# equaliser_TDA7418.net
KiCad netlist of a schematic drawn in EAGLE
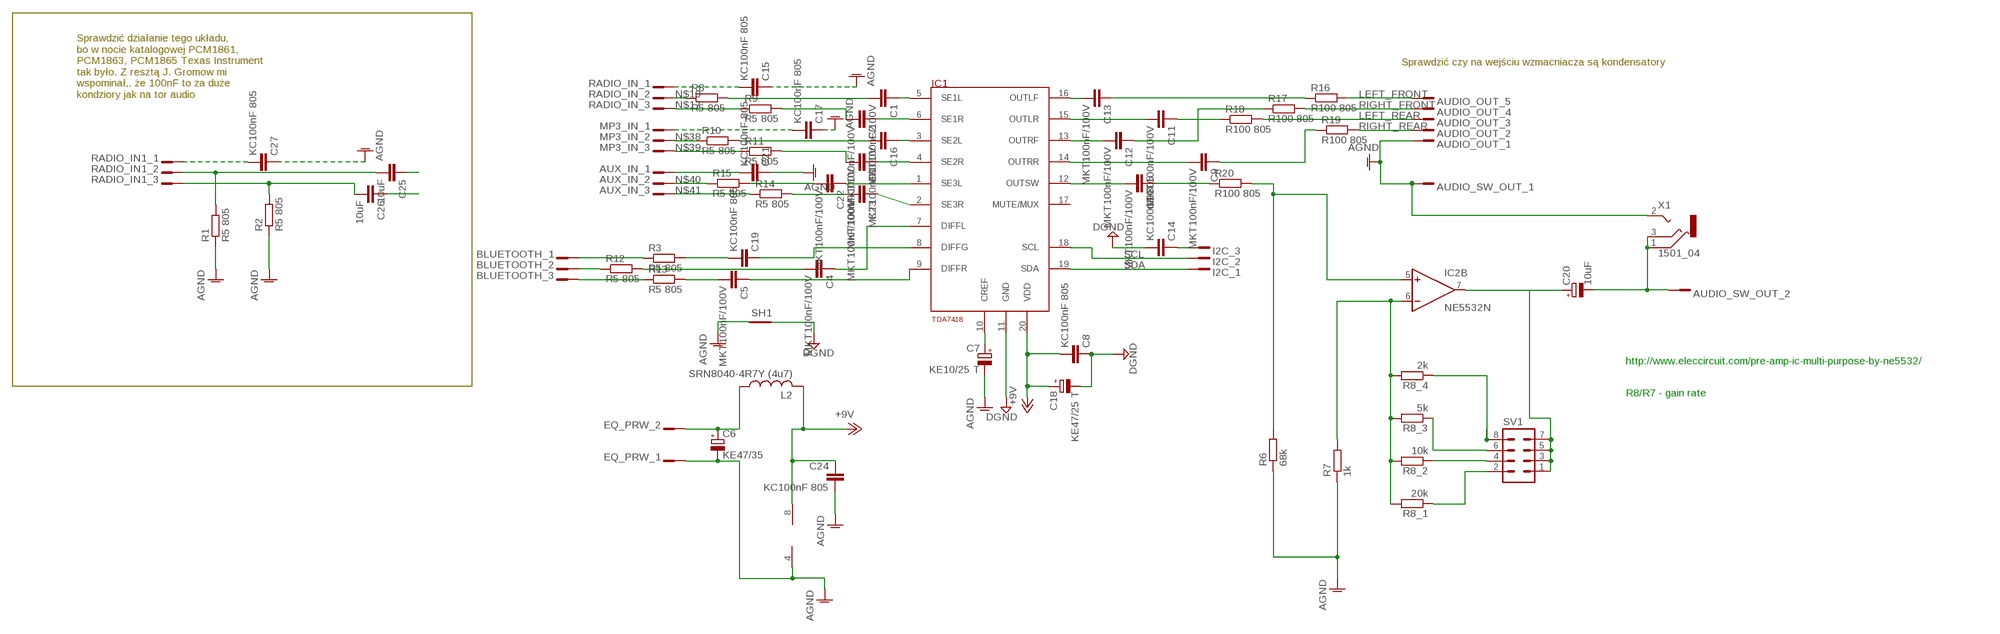
[diagram p0: schematic, sheet 1]

(export (version "E")
  (design (tool "Eeschema 10.0.6"))
  (components
    (comp (ref "AUDIO_OUT")
      (value "JST_5_PIN_B5B-PH-KS")
      (footprint "eagle-import:B5B-PH-KS")
      (libsource (lib "eagle-import") (part "JST_5_PIN_B5B-PH-KS"))
    )
    (comp (ref "AUDIO_SW_OUT")
      (value "JST_2_PIN_B2B-PH-KS")
      (footprint "eagle-import:B2B-PH-KS")
      (libsource (lib "eagle-import") (part "JST_2_PIN_B2B-PH-KS"))
    )
    (comp (ref "AUX_IN")
      (value "JST_3_PIN_B3B-PH-KS")
      (footprint "eagle-import:B3B-PH-KS")
      (libsource (lib "eagle-import") (part "JST_3_PIN_B3B-PH-KS"))
    )
    (comp (ref "BLUETOOTH")
      (value "JST_3_PIN_B3B-PH-KS")
      (footprint "eagle-import:B3B-PH-KS")
      (libsource (lib "eagle-import") (part "JST_3_PIN_B3B-PH-KS"))
    )
    (comp (ref "C1")
      (value "MKT100nF/100V")
      (footprint "eagle-import:C050-035X075")
      (libsource (lib "eagle-import") (part "C-EU050-035X075"))
    )
    (comp (ref "C2")
      (value "MKT100nF/100V")
      (footprint "eagle-import:C050-035X075")
      (libsource (lib "eagle-import") (part "C-EU050-035X075"))
    )
    (comp (ref "C3")
      (value "MKT100nF/100V")
      (footprint "eagle-import:C050-035X075")
      (libsource (lib "eagle-import") (part "C-EU050-035X075"))
    )
    (comp (ref "C4")
      (value "MKT100nF/100V")
      (footprint "eagle-import:C050-035X075")
      (libsource (lib "eagle-import") (part "C-EU050-035X075"))
    )
    (comp (ref "C5")
      (value "MKT100nF/100V")
      (footprint "eagle-import:C050-035X075")
      (libsource (lib "eagle-import") (part "C-EU050-035X075"))
    )
    (comp (ref "C6")
      (value "KE47/35")
      (footprint "eagle-import:TT2D6")
      (libsource (lib "eagle-import") (part "CPOL-EUTT2D6"))
    )
    (comp (ref "C7")
      (value "KE10/25 T")
      (footprint "eagle-import:E1,8-4")
      (libsource (lib "eagle-import") (part "resistor_CPOL-EUE1.8-4"))
    )
    (comp (ref "C8")
      (value "KC100nF 805")
      (footprint "eagle-import:C0805")
      (libsource (lib "eagle-import") (part "C-EUC0805"))
    )
    (comp (ref "C9")
      (value "MKT100nF/100V")
      (footprint "eagle-import:C050-035X075")
      (libsource (lib "eagle-import") (part "C-EU050-035X075"))
    )
    (comp (ref "C10")
      (value "MKT100nF/100V")
      (footprint "eagle-import:C050-035X075")
      (libsource (lib "eagle-import") (part "C-EU050-035X075"))
    )
    (comp (ref "C11")
      (value "MKT100nF/100V")
      (footprint "eagle-import:C050-035X075")
      (libsource (lib "eagle-import") (part "C-EU050-035X075"))
    )
    (comp (ref "C12")
      (value "MKT100nF/100V")
      (footprint "eagle-import:C050-035X075")
      (libsource (lib "eagle-import") (part "C-EU050-035X075"))
    )
    (comp (ref "C13")
      (value "MKT100nF/100V")
      (footprint "eagle-import:C050-035X075")
      (libsource (lib "eagle-import") (part "C-EU050-035X075"))
    )
    (comp (ref "C14")
      (value "KC100nF 805")
      (footprint "eagle-import:C0805")
      (libsource (lib "eagle-import") (part "C-EUC0805"))
    )
    (comp (ref "C15")
      (value "KC100nF 805")
      (footprint "eagle-import:C0805")
      (libsource (lib "eagle-import") (part "C-EUC0805"))
    )
    (comp (ref "C16")
      (value "MKT100nF/100V")
      (footprint "eagle-import:C050-035X075")
      (libsource (lib "eagle-import") (part "C-EU050-035X075"))
    )
    (comp (ref "C17")
      (value "KC100nF 805")
      (footprint "eagle-import:C0805")
      (libsource (lib "eagle-import") (part "C-EUC0805"))
    )
    (comp (ref "C18")
      (value "KE47/25 T")
      (footprint "eagle-import:B45181B")
      (libsource (lib "eagle-import") (part "CPOL-EUB45181B"))
    )
    (comp (ref "C19")
      (value "KC100nF 805")
      (footprint "eagle-import:C0805")
      (libsource (lib "eagle-import") (part "C-EUC0805"))
    )
    (comp (ref "C20")
      (value "10uF")
      (footprint "eagle-import:TT2D6")
      (libsource (lib "eagle-import") (part "CPOL-EUTT2D6"))
    )
    (comp (ref "C21")
      (value "KC100nF 805")
      (footprint "eagle-import:C0805")
      (libsource (lib "eagle-import") (part "C-EUC0805"))
    )
    (comp (ref "C22")
      (value "MKT100nF/100V")
      (footprint "eagle-import:C050-035X075")
      (libsource (lib "eagle-import") (part "C-EU050-035X075"))
    )
    (comp (ref "C23")
      (value "MKT100nF/100V")
      (footprint "eagle-import:C050-035X075")
      (libsource (lib "eagle-import") (part "C-EU050-035X075"))
    )
    (comp (ref "C24")
      (value "KC100nF 805")
      (footprint "eagle-import:C0805")
      (libsource (lib "eagle-import") (part "C-EUC0805"))
    )
    (comp (ref "C25")
      (value "10uF")
      (footprint "eagle-import:C050-035X075")
      (libsource (lib "eagle-import") (part "C-EU050-035X075"))
    )
    (comp (ref "C26")
      (value "10uF")
      (footprint "eagle-import:C050-035X075")
      (libsource (lib "eagle-import") (part "C-EU050-035X075"))
    )
    (comp (ref "C27")
      (value "KC100nF 805")
      (footprint "eagle-import:C0805")
      (libsource (lib "eagle-import") (part "C-EUC0805"))
    )
    (comp (ref "EQ_PRW")
      (value "JST_2_PIN_B2B-XH-A")
      (footprint "eagle-import:B2B-XH-A")
      (libsource (lib "eagle-import") (part "JST_2_PIN_B2B-XH-A"))
    )
    (comp (ref "I2C")
      (value "JST_3_PIN_B3B-PH-KS")
      (footprint "eagle-import:B3B-PH-KS")
      (libsource (lib "eagle-import") (part "JST_3_PIN_B3B-PH-KS"))
    )
    (comp (ref "IC1")
      (value "TDA7418")
      (footprint "eagle-import:SO20")
      (libsource (lib "eagle-import") (part "TDA7418"))
    )
    (comp (ref "IC2")
      (value "NE5532N")
      (footprint "eagle-import:DIL08")
      (libsource (lib "eagle-import") (part "NE5532N"))
    )
    (comp (ref "L2")
      (value "SRN8040-4R7Y (4u7)")
      (footprint "eagle-import:0204_5")
      (libsource (lib "eagle-import") (part "L-US0204/5"))
    )
    (comp (ref "MP3_IN")
      (value "JST_3_PIN_B3B-PH-KS")
      (footprint "eagle-import:B3B-PH-KS")
      (libsource (lib "eagle-import") (part "JST_3_PIN_B3B-PH-KS"))
    )
    (comp (ref "R1")
      (value "R5 805")
      (footprint "eagle-import:R0805")
      (libsource (lib "eagle-import") (part "R-EU_R0805"))
    )
    (comp (ref "R2")
      (value "R5 805")
      (footprint "eagle-import:R0805")
      (libsource (lib "eagle-import") (part "R-EU_R0805"))
    )
    (comp (ref "R3")
      (value "R5 805")
      (footprint "eagle-import:R0805")
      (libsource (lib "eagle-import") (part "R-EU_R0805"))
    )
    (comp (ref "R6")
      (value "68k")
      (footprint "eagle-import:R0805")
      (libsource (lib "eagle-import") (part "R-EU_R0805"))
    )
    (comp (ref "R7")
      (value "1k")
      (footprint "eagle-import:R0805")
      (libsource (lib "eagle-import") (part "R-EU_R0805"))
    )
    (comp (ref "R8")
      (value "R5 805")
      (footprint "eagle-import:R0805")
      (libsource (lib "eagle-import") (part "R-EU_R0805"))
    )
    (comp (ref "R8_1")
      (value "20k")
      (footprint "eagle-import:R0805")
      (libsource (lib "eagle-import") (part "R-EU_R0805"))
    )
    (comp (ref "R8_2")
      (value "10k")
      (footprint "eagle-import:R0805")
      (libsource (lib "eagle-import") (part "R-EU_R0805"))
    )
    (comp (ref "R8_3")
      (value "5k")
      (footprint "eagle-import:R0805")
      (libsource (lib "eagle-import") (part "R-EU_R0805"))
    )
    (comp (ref "R8_4")
      (value "2k")
      (footprint "eagle-import:R0805")
      (libsource (lib "eagle-import") (part "R-EU_R0805"))
    )
    (comp (ref "R9")
      (value "R5 805")
      (footprint "eagle-import:R0805")
      (libsource (lib "eagle-import") (part "R-EU_R0805"))
    )
    (comp (ref "R10")
      (value "R5 805")
      (footprint "eagle-import:R0805")
      (libsource (lib "eagle-import") (part "R-EU_R0805"))
    )
    (comp (ref "R11")
      (value "R5 805")
      (footprint "eagle-import:R0805")
      (libsource (lib "eagle-import") (part "R-EU_R0805"))
    )
    (comp (ref "R12")
      (value "R5 805")
      (footprint "eagle-import:R0805")
      (libsource (lib "eagle-import") (part "R-EU_R0805"))
    )
    (comp (ref "R13")
      (value "R5 805")
      (footprint "eagle-import:R0805")
      (libsource (lib "eagle-import") (part "R-EU_R0805"))
    )
    (comp (ref "R14")
      (value "R5 805")
      (footprint "eagle-import:R0805")
      (libsource (lib "eagle-import") (part "R-EU_R0805"))
    )
    (comp (ref "R15")
      (value "R5 805")
      (footprint "eagle-import:R0805")
      (libsource (lib "eagle-import") (part "R-EU_R0805"))
    )
    (comp (ref "R16")
      (value "R100 805")
      (footprint "eagle-import:R0805")
      (libsource (lib "eagle-import") (part "R-EU_R0805"))
    )
    (comp (ref "R17")
      (value "R100 805")
      (footprint "eagle-import:R0805")
      (libsource (lib "eagle-import") (part "R-EU_R0805"))
    )
    (comp (ref "R18")
      (value "R100 805")
      (footprint "eagle-import:R0805")
      (libsource (lib "eagle-import") (part "R-EU_R0805"))
    )
    (comp (ref "R19")
      (value "R100 805")
      (footprint "eagle-import:R0805")
      (libsource (lib "eagle-import") (part "R-EU_R0805"))
    )
    (comp (ref "R20")
      (value "R100 805")
      (footprint "eagle-import:R0805")
      (libsource (lib "eagle-import") (part "R-EU_R0805"))
    )
    (comp (ref "RADIO_IN")
      (value "JST_3_PIN_B3B-PH-KS")
      (footprint "eagle-import:B3B-PH-KS")
      (libsource (lib "eagle-import") (part "JST_3_PIN_B3B-PH-KS"))
    )
    (comp (ref "RADIO_IN1")
      (value "JST_3_PIN_B3B-PH-KS")
      (footprint "eagle-import:B3B-PH-KS")
      (libsource (lib "eagle-import") (part "JST_3_PIN_B3B-PH-KS"))
    )
    (comp (ref "SH1")
      (value "SHORT-HT5")
      (footprint "eagle-import:SHORT_TOP-50")
      (libsource (lib "eagle-import") (part "SHORT-HT5"))
    )
    (comp (ref "SV1")
      (value "MA04-2")
      (footprint "eagle-import:MA04-2")
      (libsource (lib "eagle-import") (part "MA04-2"))
    )
    (comp (ref "X1")
      (value "1501_04")
      (footprint "eagle-import:1501_05")
      (libsource (lib "eagle-import") (part "1501_04"))
    )
  )
  (nets
    (net (code "1") (name "+9V") (class "Default")
      (node (ref "C18") (pin "+") (pinfunction "+_+") (pintype "passive"))
      (node (ref "C24") (pin "1") (pinfunction "1_1") (pintype "passive"))
      (node (ref "C8") (pin "2") (pinfunction "2_2") (pintype "passive"))
      (node (ref "IC1") (pin "20") (pinfunction "VDD_20") (pintype "bidirectional"))
      (node (ref "IC2") (pin "8") (pinfunction "V+_8") (pintype "power_in"))
      (node (ref "L2") (pin "2") (pinfunction "2_2") (pintype "passive"))
    )
    (net (code "2") (name "/LEFT_FRONT") (class "Default")
      (node (ref "AUDIO_OUT") (pin "P$5") (pinfunction "P$1_P$5") (pintype "bidirectional"))
      (node (ref "R16") (pin "2") (pinfunction "2_2") (pintype "passive"))
    )
    (net (code "3") (name "/LEFT_REAR") (class "Default")
      (node (ref "AUDIO_OUT") (pin "P$3") (pinfunction "P$1_P$3") (pintype "bidirectional"))
      (node (ref "R18") (pin "2") (pinfunction "2_2") (pintype "passive"))
    )
    (net (code "4") (name "/N$10") (class "Default")
      (node (ref "R8") (pin "1") (pinfunction "1_1") (pintype "passive"))
      (node (ref "RADIO_IN") (pin "P$2") (pinfunction "P$1_P$2") (pintype "bidirectional"))
    )
    (net (code "5") (name "/N$17") (class "Default")
      (node (ref "R9") (pin "1") (pinfunction "1_1") (pintype "passive"))
      (node (ref "RADIO_IN") (pin "P$3") (pinfunction "P$1_P$3") (pintype "bidirectional"))
    )
    (net (code "6") (name "/N$38") (class "Default")
      (node (ref "MP3_IN") (pin "P$2") (pinfunction "P$1_P$2") (pintype "bidirectional"))
      (node (ref "R10") (pin "1") (pinfunction "1_1") (pintype "passive"))
    )
    (net (code "7") (name "/N$39") (class "Default")
      (node (ref "MP3_IN") (pin "P$3") (pinfunction "P$1_P$3") (pintype "bidirectional"))
      (node (ref "R11") (pin "1") (pinfunction "1_1") (pintype "passive"))
    )
    (net (code "8") (name "/N$40") (class "Default")
      (node (ref "BLUETOOTH") (pin "P$2") (pinfunction "P$1_P$2") (pintype "bidirectional"))
      (node (ref "R12") (pin "1") (pinfunction "1_1") (pintype "passive"))
    )
    (net (code "9") (name "/N$41") (class "Default")
      (node (ref "BLUETOOTH") (pin "P$3") (pinfunction "P$1_P$3") (pintype "bidirectional"))
      (node (ref "R13") (pin "1") (pinfunction "1_1") (pintype "passive"))
    )
    (net (code "10") (name "/RIGHT_FRONT") (class "Default")
      (node (ref "AUDIO_OUT") (pin "P$4") (pinfunction "P$1_P$4") (pintype "bidirectional"))
      (node (ref "R17") (pin "2") (pinfunction "2_2") (pintype "passive"))
    )
    (net (code "11") (name "/RIGHT_REAR") (class "Default")
      (node (ref "AUDIO_OUT") (pin "P$2") (pinfunction "P$1_P$2") (pintype "bidirectional"))
      (node (ref "R19") (pin "2") (pinfunction "2_2") (pintype "passive"))
    )
    (net (code "12") (name "/SCL") (class "Default")
      (node (ref "I2C") (pin "P$2") (pinfunction "P$1_P$2") (pintype "bidirectional"))
      (node (ref "IC1") (pin "18") (pinfunction "SCL_18") (pintype "bidirectional"))
    )
    (net (code "13") (name "/SDA") (class "Default")
      (node (ref "I2C") (pin "P$1") (pinfunction "P$1_P$1") (pintype "bidirectional"))
      (node (ref "IC1") (pin "19") (pinfunction "SDA_19") (pintype "bidirectional"))
    )
    (net (code "14") (name "AGND") (class "Default")
      (node (ref "AUDIO_OUT") (pin "P$1") (pinfunction "P$1_P$1") (pintype "bidirectional"))
      (node (ref "AUDIO_SW_OUT") (pin "P$1") (pinfunction "P$1_P$1") (pintype "bidirectional"))
      (node (ref "C15") (pin "1") (pinfunction "1_1") (pintype "passive"))
      (node (ref "C17") (pin "1") (pinfunction "1_1") (pintype "passive"))
      (node (ref "C21") (pin "1") (pinfunction "1_1") (pintype "passive"))
      (node (ref "C24") (pin "2") (pinfunction "2_2") (pintype "passive"))
      (node (ref "C27") (pin "1") (pinfunction "1_1") (pintype "passive"))
      (node (ref "C6") (pin "-") (pinfunction "-_-") (pintype "passive"))
      (node (ref "C7") (pin "-") (pinfunction "-_-") (pintype "passive"))
      (node (ref "EQ_PRW") (pin "P$1") (pinfunction "P$1_P$1") (pintype "bidirectional"))
      (node (ref "IC2") (pin "4") (pinfunction "V-_4") (pintype "power_in"))
      (node (ref "R1") (pin "1") (pinfunction "1_1") (pintype "passive"))
      (node (ref "R2") (pin "1") (pinfunction "1_1") (pintype "passive"))
      (node (ref "R6") (pin "1") (pinfunction "1_1") (pintype "passive"))
      (node (ref "R7") (pin "1") (pinfunction "1_1") (pintype "passive"))
      (node (ref "SH1") (pin "1") (pinfunction "P$1_1") (pintype "bidirectional"))
      (node (ref "X1") (pin "2") (pinfunction "2_2") (pintype "passive"))
    )
    (net (code "15") (name "DGND") (class "Default")
      (node (ref "C14") (pin "2") (pinfunction "2_2") (pintype "passive"))
      (node (ref "C18") (pin "-") (pinfunction "-_-") (pintype "passive"))
      (node (ref "C8") (pin "1") (pinfunction "1_1") (pintype "passive"))
      (node (ref "IC1") (pin "11") (pinfunction "GND_11") (pintype "bidirectional"))
      (node (ref "SH1") (pin "2") (pinfunction "P$2_2") (pintype "bidirectional"))
    )
    (net (code "16") (name "Net-(AUDIO_SW_OUTB-P$1)") (class "Default")
      (node (ref "AUDIO_SW_OUT") (pin "P$2") (pinfunction "P$1_P$2") (pintype "bidirectional"))
      (node (ref "C20") (pin "-") (pinfunction "-_-") (pintype "passive"))
      (node (ref "X1") (pin "1") (pinfunction "1_1") (pintype "passive"))
      (node (ref "X1") (pin "3") (pinfunction "3_3") (pintype "passive"))
    )
    (net (code "17") (name "Net-(AUX_IN-PadP$1)") (class "Default")
      (node (ref "AUX_IN") (pin "P$1") (pinfunction "P$1_P$1") (pintype "bidirectional"))
      (node (ref "C21") (pin "2") (pinfunction "2_2") (pintype "passive"))
    )
    (net (code "18") (name "Net-(AUX_INB-P$1)") (class "Default")
      (node (ref "AUX_IN") (pin "P$2") (pinfunction "P$1_P$2") (pintype "bidirectional"))
      (node (ref "R15") (pin "1") (pinfunction "1_1") (pintype "passive"))
    )
    (net (code "19") (name "Net-(AUX_INC-P$1)") (class "Default")
      (node (ref "AUX_IN") (pin "P$3") (pinfunction "P$1_P$3") (pintype "bidirectional"))
      (node (ref "R14") (pin "1") (pinfunction "1_1") (pintype "passive"))
    )
    (net (code "20") (name "Net-(BLUETOOTH-PadP$1)") (class "Default")
      (node (ref "BLUETOOTH") (pin "P$1") (pinfunction "P$1_P$1") (pintype "bidirectional"))
      (node (ref "R3") (pin "1") (pinfunction "1_1") (pintype "passive"))
    )
    (net (code "21") (name "Net-(C1-Pad2)") (class "Default")
      (node (ref "C1") (pin "2") (pinfunction "2_2") (pintype "passive"))
      (node (ref "R8") (pin "2") (pinfunction "2_2") (pintype "passive"))
    )
    (net (code "22") (name "Net-(C2-Pad2)") (class "Default")
      (node (ref "C2") (pin "2") (pinfunction "2_2") (pintype "passive"))
      (node (ref "R9") (pin "2") (pinfunction "2_2") (pintype "passive"))
    )
    (net (code "23") (name "Net-(C3-Pad2)") (class "Default")
      (node (ref "C3") (pin "2") (pinfunction "2_2") (pintype "passive"))
      (node (ref "R11") (pin "2") (pinfunction "2_2") (pintype "passive"))
    )
    (net (code "24") (name "Net-(C4-Pad2)") (class "Default")
      (node (ref "C4") (pin "2") (pinfunction "2_2") (pintype "passive"))
      (node (ref "R12") (pin "2") (pinfunction "2_2") (pintype "passive"))
    )
    (net (code "25") (name "Net-(C5-Pad2)") (class "Default")
      (node (ref "C5") (pin "2") (pinfunction "2_2") (pintype "passive"))
      (node (ref "R13") (pin "2") (pinfunction "2_2") (pintype "passive"))
    )
    (net (code "26") (name "Net-(C9-Pad1)") (class "Default")
      (node (ref "C9") (pin "1") (pinfunction "1_1") (pintype "passive"))
      (node (ref "R19") (pin "1") (pinfunction "1_1") (pintype "passive"))
    )
    (net (code "27") (name "Net-(C10-Pad1)") (class "Default")
      (node (ref "C10") (pin "1") (pinfunction "1_1") (pintype "passive"))
      (node (ref "R20") (pin "1") (pinfunction "1_1") (pintype "passive"))
    )
    (net (code "28") (name "Net-(C11-Pad1)") (class "Default")
      (node (ref "C11") (pin "1") (pinfunction "1_1") (pintype "passive"))
      (node (ref "R18") (pin "1") (pinfunction "1_1") (pintype "passive"))
    )
    (net (code "29") (name "Net-(C12-Pad1)") (class "Default")
      (node (ref "C12") (pin "1") (pinfunction "1_1") (pintype "passive"))
      (node (ref "R17") (pin "1") (pinfunction "1_1") (pintype "passive"))
    )
    (net (code "30") (name "Net-(C13-Pad1)") (class "Default")
      (node (ref "C13") (pin "1") (pinfunction "1_1") (pintype "passive"))
      (node (ref "R16") (pin "1") (pinfunction "1_1") (pintype "passive"))
    )
    (net (code "31") (name "Net-(C15-Pad2)") (class "Default")
      (node (ref "C15") (pin "2") (pinfunction "2_2") (pintype "passive"))
      (node (ref "RADIO_IN") (pin "P$1") (pinfunction "P$1_P$1") (pintype "bidirectional"))
    )
    (net (code "32") (name "Net-(C16-Pad2)") (class "Default")
      (node (ref "C16") (pin "2") (pinfunction "2_2") (pintype "passive"))
      (node (ref "R10") (pin "2") (pinfunction "2_2") (pintype "passive"))
    )
    (net (code "33") (name "Net-(C17-Pad2)") (class "Default")
      (node (ref "C17") (pin "2") (pinfunction "2_2") (pintype "passive"))
      (node (ref "MP3_IN") (pin "P$1") (pinfunction "P$1_P$1") (pintype "bidirectional"))
    )
    (net (code "34") (name "Net-(C19-Pad2)") (class "Default")
      (node (ref "C19") (pin "2") (pinfunction "2_2") (pintype "passive"))
      (node (ref "R3") (pin "2") (pinfunction "2_2") (pintype "passive"))
    )
    (net (code "35") (name "Net-(C22-Pad2)") (class "Default")
      (node (ref "C22") (pin "2") (pinfunction "2_2") (pintype "passive"))
      (node (ref "R15") (pin "2") (pinfunction "2_2") (pintype "passive"))
    )
    (net (code "36") (name "Net-(C23-Pad2)") (class "Default")
      (node (ref "C23") (pin "2") (pinfunction "2_2") (pintype "passive"))
      (node (ref "R14") (pin "2") (pinfunction "2_2") (pintype "passive"))
    )
    (net (code "37") (name "Net-(C27-Pad2)") (class "Default")
      (node (ref "C27") (pin "2") (pinfunction "2_2") (pintype "passive"))
      (node (ref "RADIO_IN1") (pin "P$1") (pinfunction "P$1_P$1") (pintype "bidirectional"))
    )
    (net (code "38") (name "Net-(EQ_PRWB-P$1)") (class "Default")
      (node (ref "C6") (pin "+") (pinfunction "+_+") (pintype "passive"))
      (node (ref "EQ_PRW") (pin "P$2") (pinfunction "P$1_P$2") (pintype "bidirectional"))
      (node (ref "L2") (pin "1") (pinfunction "1_1") (pintype "passive"))
    )
    (net (code "39") (name "Net-(I2CC-P$1)") (class "Default")
      (node (ref "C14") (pin "1") (pinfunction "1_1") (pintype "passive"))
      (node (ref "I2C") (pin "P$3") (pinfunction "P$1_P$3") (pintype "bidirectional"))
    )
    (net (code "40") (name "Net-(IC1-CREF)") (class "Default")
      (node (ref "C7") (pin "+") (pinfunction "+_+") (pintype "passive"))
      (node (ref "IC1") (pin "10") (pinfunction "CREF_10") (pintype "bidirectional"))
    )
    (net (code "41") (name "Net-(IC1-DIFFG)") (class "Default")
      (node (ref "C19") (pin "1") (pinfunction "1_1") (pintype "passive"))
      (node (ref "IC1") (pin "8") (pinfunction "DIFFG_8") (pintype "bidirectional"))
    )
    (net (code "42") (name "Net-(IC1-DIFFL)") (class "Default")
      (node (ref "C4") (pin "1") (pinfunction "1_1") (pintype "passive"))
      (node (ref "IC1") (pin "7") (pinfunction "DIFFL_7") (pintype "bidirectional"))
    )
    (net (code "43") (name "Net-(IC1-DIFFR)") (class "Default")
      (node (ref "C5") (pin "1") (pinfunction "1_1") (pintype "passive"))
      (node (ref "IC1") (pin "9") (pinfunction "DIFFR_9") (pintype "bidirectional"))
    )
    (net (code "44") (name "Net-(IC1-OUTLF)") (class "Default")
      (node (ref "C13") (pin "2") (pinfunction "2_2") (pintype "passive"))
      (node (ref "IC1") (pin "16") (pinfunction "OUTLF_16") (pintype "bidirectional"))
    )
    (net (code "45") (name "Net-(IC1-OUTLR)") (class "Default")
      (node (ref "C11") (pin "2") (pinfunction "2_2") (pintype "passive"))
      (node (ref "IC1") (pin "15") (pinfunction "OUTLR_15") (pintype "bidirectional"))
    )
    (net (code "46") (name "Net-(IC1-OUTRF)") (class "Default")
      (node (ref "C12") (pin "2") (pinfunction "2_2") (pintype "passive"))
      (node (ref "IC1") (pin "13") (pinfunction "OUTRF_13") (pintype "bidirectional"))
    )
    (net (code "47") (name "Net-(IC1-OUTRR)") (class "Default")
      (node (ref "C9") (pin "2") (pinfunction "2_2") (pintype "passive"))
      (node (ref "IC1") (pin "14") (pinfunction "OUTRR_14") (pintype "bidirectional"))
    )
    (net (code "48") (name "Net-(IC1-OUTSW)") (class "Default")
      (node (ref "C10") (pin "2") (pinfunction "2_2") (pintype "passive"))
      (node (ref "IC1") (pin "12") (pinfunction "OUTSW_12") (pintype "bidirectional"))
    )
    (net (code "49") (name "Net-(IC1-SE1L)") (class "Default")
      (node (ref "C1") (pin "1") (pinfunction "1_1") (pintype "passive"))
      (node (ref "IC1") (pin "5") (pinfunction "SE1L_5") (pintype "bidirectional"))
    )
    (net (code "50") (name "Net-(IC1-SE1R)") (class "Default")
      (node (ref "C2") (pin "1") (pinfunction "1_1") (pintype "passive"))
      (node (ref "IC1") (pin "6") (pinfunction "SE1R_6") (pintype "bidirectional"))
    )
    (net (code "51") (name "Net-(IC1-SE2L)") (class "Default")
      (node (ref "C16") (pin "1") (pinfunction "1_1") (pintype "passive"))
      (node (ref "IC1") (pin "3") (pinfunction "SE2L_3") (pintype "bidirectional"))
    )
    (net (code "52") (name "Net-(IC1-SE2R)") (class "Default")
      (node (ref "C3") (pin "1") (pinfunction "1_1") (pintype "passive"))
      (node (ref "IC1") (pin "4") (pinfunction "SE2R_4") (pintype "bidirectional"))
    )
    (net (code "53") (name "Net-(IC1-SE3L)") (class "Default")
      (node (ref "C22") (pin "1") (pinfunction "1_1") (pintype "passive"))
      (node (ref "IC1") (pin "1") (pinfunction "SE3L_1") (pintype "bidirectional"))
    )
    (net (code "54") (name "Net-(IC1-SE3R)") (class "Default")
      (node (ref "C23") (pin "1") (pinfunction "1_1") (pintype "passive"))
      (node (ref "IC1") (pin "2") (pinfunction "SE3R_2") (pintype "bidirectional"))
    )
    (net (code "55") (name "Net-(IC2B-+IN)") (class "Default")
      (node (ref "IC2") (pin "5") (pinfunction "+IN_5") (pintype "input"))
      (node (ref "R20") (pin "2") (pinfunction "2_2") (pintype "passive"))
      (node (ref "R6") (pin "2") (pinfunction "2_2") (pintype "passive"))
    )
    (net (code "56") (name "Net-(IC2B--IN)") (class "Default")
      (node (ref "IC2") (pin "6") (pinfunction "-IN_6") (pintype "input"))
      (node (ref "R7") (pin "2") (pinfunction "2_2") (pintype "passive"))
      (node (ref "R8_1") (pin "2") (pinfunction "2_2") (pintype "passive"))
      (node (ref "R8_2") (pin "2") (pinfunction "2_2") (pintype "passive"))
      (node (ref "R8_3") (pin "2") (pinfunction "2_2") (pintype "passive"))
      (node (ref "R8_4") (pin "2") (pinfunction "2_2") (pintype "passive"))
    )
    (net (code "57") (name "Net-(IC2B-OUT)") (class "Default")
      (node (ref "C20") (pin "+") (pinfunction "+_+") (pintype "passive"))
      (node (ref "IC2") (pin "7") (pinfunction "OUT_7") (pintype "output"))
      (node (ref "SV1") (pin "1") (pinfunction "1_1") (pintype "passive"))
      (node (ref "SV1") (pin "3") (pinfunction "3_3") (pintype "passive"))
      (node (ref "SV1") (pin "5") (pinfunction "5_5") (pintype "passive"))
      (node (ref "SV1") (pin "7") (pinfunction "7_7") (pintype "passive"))
    )
    (net (code "58") (name "Net-(R8_1-Pad1)") (class "Default")
      (node (ref "R8_1") (pin "1") (pinfunction "1_1") (pintype "passive"))
      (node (ref "SV1") (pin "2") (pinfunction "2_2") (pintype "passive"))
    )
    (net (code "59") (name "Net-(R8_2-Pad1)") (class "Default")
      (node (ref "R8_2") (pin "1") (pinfunction "1_1") (pintype "passive"))
      (node (ref "SV1") (pin "4") (pinfunction "4_4") (pintype "passive"))
    )
    (net (code "60") (name "Net-(R8_3-Pad1)") (class "Default")
      (node (ref "R8_3") (pin "1") (pinfunction "1_1") (pintype "passive"))
      (node (ref "SV1") (pin "6") (pinfunction "6_6") (pintype "passive"))
    )
    (net (code "61") (name "Net-(R8_4-Pad1)") (class "Default")
      (node (ref "R8_4") (pin "1") (pinfunction "1_1") (pintype "passive"))
      (node (ref "SV1") (pin "8") (pinfunction "8_8") (pintype "passive"))
    )
    (net (code "62") (name "Net-(RADIO_IN1B-P$1)") (class "Default")
      (node (ref "C25") (pin "2") (pinfunction "2_2") (pintype "passive"))
      (node (ref "R1") (pin "2") (pinfunction "2_2") (pintype "passive"))
      (node (ref "RADIO_IN1") (pin "P$2") (pinfunction "P$1_P$2") (pintype "bidirectional"))
    )
    (net (code "63") (name "Net-(RADIO_IN1C-P$1)") (class "Default")
      (node (ref "C26") (pin "2") (pinfunction "2_2") (pintype "passive"))
      (node (ref "R2") (pin "2") (pinfunction "2_2") (pintype "passive"))
      (node (ref "RADIO_IN1") (pin "P$3") (pinfunction "P$1_P$3") (pintype "bidirectional"))
    )
    (net (code "64") (name "unconnected-(C25-Pad1)") (class "Default")
      (node (ref "C25") (pin "1") (pinfunction "1_1") (pintype "passive"))
    )
    (net (code "65") (name "unconnected-(C26-Pad1)") (class "Default")
      (node (ref "C26") (pin "1") (pinfunction "1_1") (pintype "passive"))
    )
    (net (code "66") (name "unconnected-(IC1-MUTE{slash}MUX-Pad17)") (class "Default")
      (node (ref "IC1") (pin "17") (pinfunction "MUTE/MUX_17") (pintype "bidirectional"))
    )
  )
)
